# ESP32_S3.net
KiCad netlist of a schematic drawn in EasyEDA Pro
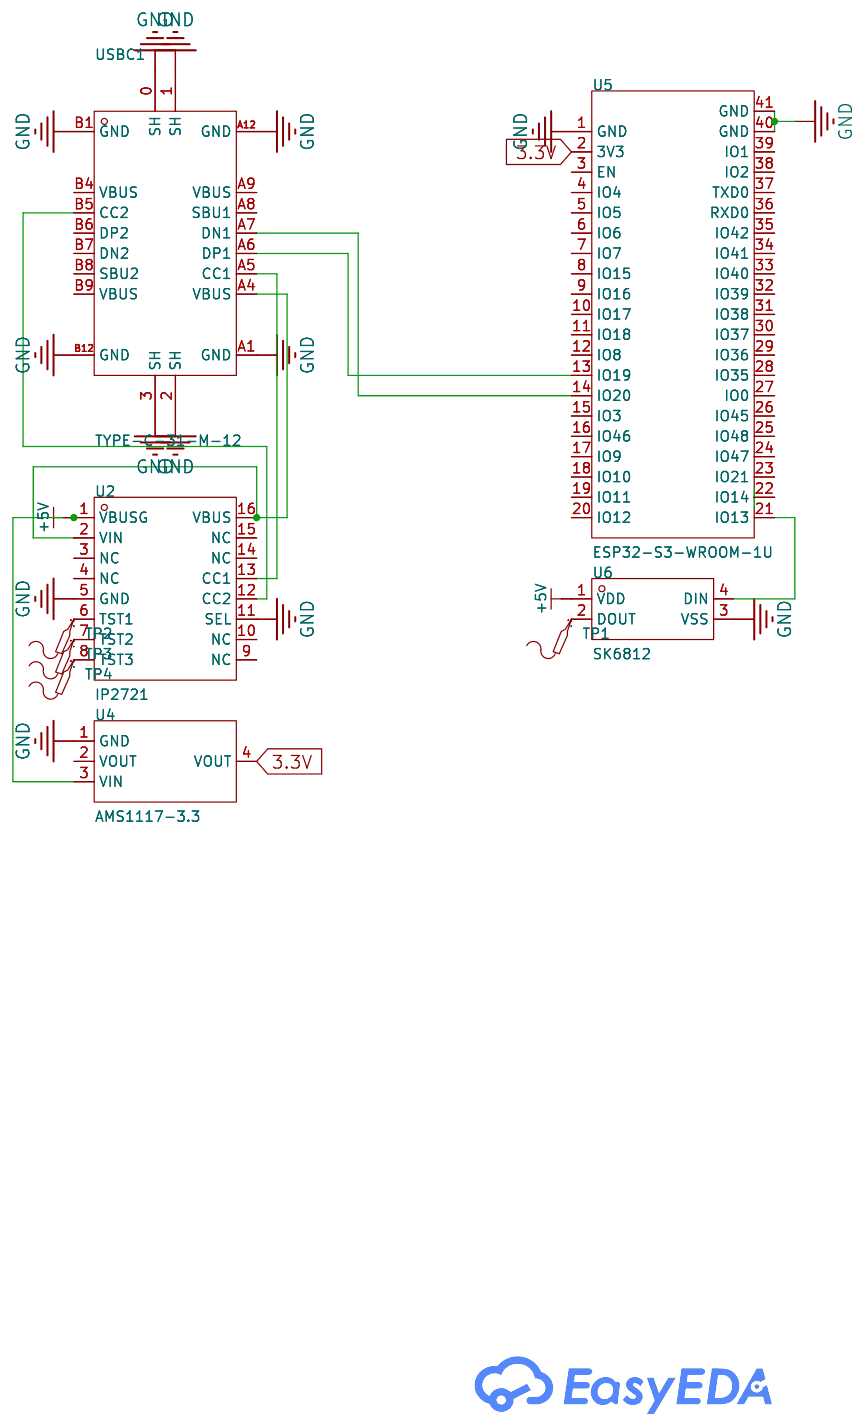
[diagram p0: schematic sheet]

(export (version "E")
  (design (tool "Eeschema 10.0.6"))
  (components
    (comp (ref "TP1")
      (value "~")
      (footprint "easyedapro:Test-Point-0.5mm")
      (description "Test Point 测试点")
      (libsource (lib "easyedapro") (part "Test-Point"))
    )
    (comp (ref "TP2")
      (value "~")
      (footprint "easyedapro:Test-Point-0.5mm")
      (description "Test Point 测试点")
      (libsource (lib "easyedapro") (part "Test-Point"))
    )
    (comp (ref "TP3")
      (value "~")
      (footprint "easyedapro:Test-Point-0.5mm")
      (description "Test Point 测试点")
      (libsource (lib "easyedapro") (part "Test-Point"))
    )
    (comp (ref "TP4")
      (value "~")
      (footprint "easyedapro:Test-Point-0.5mm")
      (description "Test Point 测试点")
      (libsource (lib "easyedapro") (part "Test-Point"))
    )
    (comp (ref "U2")
      (value "IP2721")
      (footprint "easyedapro:TSSOP-16_L5.0-W4.4-P0.65-LS6.4-BL")
      (fields (field (name "Manufacturer") "INJOINIC(英集芯)"))
      (libsource (lib "easyedapro") (part "IP2721"))
    )
    (comp (ref "U4")
      (value "AMS1117-3.3")
      (footprint "easyedapro:SOT-223-3_L6.5-W3.4-P2.30-LS7.0-BR")
      (fields (field (name "Manufacturer") "AMS"))
      (libsource (lib "easyedapro") (part "AMS1117-3.3"))
    )
    (comp (ref "U5")
      (value "ESP32-S3-WROOM-1U")
      (footprint "easyedapro:WIRELM-SMD_ESP32-S3-WROOM-1U")
      (libsource (lib "easyedapro") (part "ESP32-S3-WROOM-1U"))
    )
    (comp (ref "U6")
      (value "SK6812")
      (footprint "easyedapro:LED-SMD_4P-L5.0-W5.0-TL")
      (libsource (lib "easyedapro") (part "SK6812"))
    )
    (comp (ref "USBC1")
      (value "TYPE-C-31-M-12")
      (footprint "easyedapro:USB-C_SMD-TYPE-C-31-M-12")
      (fields (field (name "Manufacturer") "韩国韩荣"))
      (libsource (lib "easyedapro") (part "TYPE-C-31-M-12"))
    )
  )
  (nets
    (net (code "1") (name "+5V") (class "Default")
      (node (ref "U2") (pin "1") (pinfunction "VBUSG_1") (pintype "unspecified"))
      (node (ref "U4") (pin "3") (pinfunction "VIN_3") (pintype "unspecified"))
      (node (ref "U6") (pin "1") (pinfunction "VDD_1") (pintype "unspecified"))
    )
    (net (code "2") (name "3.3V") (class "Default")
      (node (ref "U4") (pin "4") (pinfunction "VOUT_4") (pintype "unspecified"))
      (node (ref "U5") (pin "2") (pinfunction "3V3_2") (pintype "unspecified"))
    )
    (net (code "3") (name "GND") (class "Default")
      (node (ref "U2") (pin "11") (pinfunction "SEL_11") (pintype "unspecified"))
      (node (ref "U2") (pin "5") (pinfunction "GND_5") (pintype "unspecified"))
      (node (ref "U4") (pin "1") (pinfunction "GND_1") (pintype "unspecified"))
      (node (ref "U5") (pin "1") (pinfunction "GND_1") (pintype "unspecified"))
      (node (ref "U5") (pin "40") (pinfunction "GND_40") (pintype "unspecified"))
      (node (ref "U5") (pin "41") (pinfunction "GND_41") (pintype "unspecified"))
      (node (ref "U6") (pin "3") (pinfunction "VSS_3") (pintype "unspecified"))
      (node (ref "USBC1") (pin "0") (pinfunction "SH_0") (pintype "unspecified"))
      (node (ref "USBC1") (pin "1") (pinfunction "SH_1") (pintype "unspecified"))
      (node (ref "USBC1") (pin "2") (pinfunction "SH_2") (pintype "unspecified"))
      (node (ref "USBC1") (pin "3") (pinfunction "SH_3") (pintype "unspecified"))
      (node (ref "USBC1") (pin "A1") (pinfunction "GND_A1") (pintype "unspecified"))
      (node (ref "USBC1") (pin "A12") (pinfunction "GND_A12") (pintype "unspecified"))
      (node (ref "USBC1") (pin "B1") (pinfunction "GND_B1") (pintype "unspecified"))
      (node (ref "USBC1") (pin "B12") (pinfunction "GND_B12") (pintype "unspecified"))
    )
    (net (code "4") (name "Net-(U2-CC1)") (class "Default")
      (node (ref "U2") (pin "13") (pinfunction "CC1_13") (pintype "unspecified"))
      (node (ref "USBC1") (pin "A5") (pinfunction "CC1_A5") (pintype "unspecified"))
    )
    (net (code "5") (name "Net-(U2-CC2)") (class "Default")
      (node (ref "U2") (pin "12") (pinfunction "CC2_12") (pintype "unspecified"))
      (node (ref "USBC1") (pin "B5") (pinfunction "CC2_B5") (pintype "unspecified"))
    )
    (net (code "6") (name "Net-(U2-TST1)") (class "Default")
      (node (ref "TP2") (pin "1") (pinfunction "1_1") (pintype "unspecified"))
      (node (ref "U2") (pin "6") (pinfunction "TST1_6") (pintype "unspecified"))
    )
    (net (code "7") (name "Net-(U2-TST2)") (class "Default")
      (node (ref "TP3") (pin "1") (pinfunction "1_1") (pintype "unspecified"))
      (node (ref "U2") (pin "7") (pinfunction "TST2_7") (pintype "unspecified"))
    )
    (net (code "8") (name "Net-(U2-TST3)") (class "Default")
      (node (ref "TP4") (pin "1") (pinfunction "1_1") (pintype "unspecified"))
      (node (ref "U2") (pin "8") (pinfunction "TST3_8") (pintype "unspecified"))
    )
    (net (code "9") (name "Net-(U2-VBUS)") (class "Default")
      (node (ref "U2") (pin "16") (pinfunction "VBUS_16") (pintype "unspecified"))
      (node (ref "U2") (pin "2") (pinfunction "VIN_2") (pintype "unspecified"))
      (node (ref "USBC1") (pin "A4") (pinfunction "VBUS_A4") (pintype "unspecified"))
    )
    (net (code "10") (name "Net-(U5-IO13)") (class "Default")
      (node (ref "U5") (pin "21") (pinfunction "IO13_21") (pintype "unspecified"))
      (node (ref "U6") (pin "4") (pinfunction "DIN_4") (pintype "unspecified"))
    )
    (net (code "11") (name "Net-(U5-IO19)") (class "Default")
      (node (ref "U5") (pin "13") (pinfunction "IO19_13") (pintype "unspecified"))
      (node (ref "USBC1") (pin "A6") (pinfunction "DP1_A6") (pintype "unspecified"))
    )
    (net (code "12") (name "Net-(U5-IO20)") (class "Default")
      (node (ref "U5") (pin "14") (pinfunction "IO20_14") (pintype "unspecified"))
      (node (ref "USBC1") (pin "A7") (pinfunction "DN1_A7") (pintype "unspecified"))
    )
    (net (code "13") (name "Net-(U6-DOUT)") (class "Default")
      (node (ref "TP1") (pin "1") (pinfunction "1_1") (pintype "unspecified"))
      (node (ref "U6") (pin "2") (pinfunction "DOUT_2") (pintype "unspecified"))
    )
    (net (code "14") (name "unconnected-(U2-NC-Pad3)") (class "Default")
      (node (ref "U2") (pin "3") (pinfunction "NC_3") (pintype "unspecified"))
    )
    (net (code "15") (name "unconnected-(U2-NC-Pad4)") (class "Default")
      (node (ref "U2") (pin "4") (pinfunction "NC_4") (pintype "unspecified"))
    )
    (net (code "16") (name "unconnected-(U2-NC-Pad9)") (class "Default")
      (node (ref "U2") (pin "9") (pinfunction "NC_9") (pintype "unspecified"))
    )
    (net (code "17") (name "unconnected-(U2-NC-Pad10)") (class "Default")
      (node (ref "U2") (pin "10") (pinfunction "NC_10") (pintype "unspecified"))
    )
    (net (code "18") (name "unconnected-(U2-NC-Pad14)") (class "Default")
      (node (ref "U2") (pin "14") (pinfunction "NC_14") (pintype "unspecified"))
    )
    (net (code "19") (name "unconnected-(U2-NC-Pad15)") (class "Default")
      (node (ref "U2") (pin "15") (pinfunction "NC_15") (pintype "unspecified"))
    )
    (net (code "20") (name "unconnected-(U4-VOUT-Pad2)") (class "Default")
      (node (ref "U4") (pin "2") (pinfunction "VOUT_2") (pintype "unspecified"))
    )
    (net (code "21") (name "unconnected-(U5-EN-Pad3)") (class "Default")
      (node (ref "U5") (pin "3") (pinfunction "EN_3") (pintype "unspecified"))
    )
    (net (code "22") (name "unconnected-(U5-IO0-Pad27)") (class "Default")
      (node (ref "U5") (pin "27") (pinfunction "IO0_27") (pintype "unspecified"))
    )
    (net (code "23") (name "unconnected-(U5-IO1-Pad39)") (class "Default")
      (node (ref "U5") (pin "39") (pinfunction "IO1_39") (pintype "unspecified"))
    )
    (net (code "24") (name "unconnected-(U5-IO2-Pad38)") (class "Default")
      (node (ref "U5") (pin "38") (pinfunction "IO2_38") (pintype "unspecified"))
    )
    (net (code "25") (name "unconnected-(U5-IO3-Pad15)") (class "Default")
      (node (ref "U5") (pin "15") (pinfunction "IO3_15") (pintype "unspecified"))
    )
    (net (code "26") (name "unconnected-(U5-IO4-Pad4)") (class "Default")
      (node (ref "U5") (pin "4") (pinfunction "IO4_4") (pintype "unspecified"))
    )
    (net (code "27") (name "unconnected-(U5-IO5-Pad5)") (class "Default")
      (node (ref "U5") (pin "5") (pinfunction "IO5_5") (pintype "unspecified"))
    )
    (net (code "28") (name "unconnected-(U5-IO6-Pad6)") (class "Default")
      (node (ref "U5") (pin "6") (pinfunction "IO6_6") (pintype "unspecified"))
    )
    (net (code "29") (name "unconnected-(U5-IO7-Pad7)") (class "Default")
      (node (ref "U5") (pin "7") (pinfunction "IO7_7") (pintype "unspecified"))
    )
    (net (code "30") (name "unconnected-(U5-IO8-Pad12)") (class "Default")
      (node (ref "U5") (pin "12") (pinfunction "IO8_12") (pintype "unspecified"))
    )
    (net (code "31") (name "unconnected-(U5-IO9-Pad17)") (class "Default")
      (node (ref "U5") (pin "17") (pinfunction "IO9_17") (pintype "unspecified"))
    )
    (net (code "32") (name "unconnected-(U5-IO10-Pad18)") (class "Default")
      (node (ref "U5") (pin "18") (pinfunction "IO10_18") (pintype "unspecified"))
    )
    (net (code "33") (name "unconnected-(U5-IO11-Pad19)") (class "Default")
      (node (ref "U5") (pin "19") (pinfunction "IO11_19") (pintype "unspecified"))
    )
    (net (code "34") (name "unconnected-(U5-IO12-Pad20)") (class "Default")
      (node (ref "U5") (pin "20") (pinfunction "IO12_20") (pintype "unspecified"))
    )
    (net (code "35") (name "unconnected-(U5-IO14-Pad22)") (class "Default")
      (node (ref "U5") (pin "22") (pinfunction "IO14_22") (pintype "unspecified"))
    )
    (net (code "36") (name "unconnected-(U5-IO15-Pad8)") (class "Default")
      (node (ref "U5") (pin "8") (pinfunction "IO15_8") (pintype "unspecified"))
    )
    (net (code "37") (name "unconnected-(U5-IO16-Pad9)") (class "Default")
      (node (ref "U5") (pin "9") (pinfunction "IO16_9") (pintype "unspecified"))
    )
    (net (code "38") (name "unconnected-(U5-IO17-Pad10)") (class "Default")
      (node (ref "U5") (pin "10") (pinfunction "IO17_10") (pintype "unspecified"))
    )
    (net (code "39") (name "unconnected-(U5-IO18-Pad11)") (class "Default")
      (node (ref "U5") (pin "11") (pinfunction "IO18_11") (pintype "unspecified"))
    )
    (net (code "40") (name "unconnected-(U5-IO21-Pad23)") (class "Default")
      (node (ref "U5") (pin "23") (pinfunction "IO21_23") (pintype "unspecified"))
    )
    (net (code "41") (name "unconnected-(U5-IO35-Pad28)") (class "Default")
      (node (ref "U5") (pin "28") (pinfunction "IO35_28") (pintype "unspecified"))
    )
    (net (code "42") (name "unconnected-(U5-IO36-Pad29)") (class "Default")
      (node (ref "U5") (pin "29") (pinfunction "IO36_29") (pintype "unspecified"))
    )
    (net (code "43") (name "unconnected-(U5-IO37-Pad30)") (class "Default")
      (node (ref "U5") (pin "30") (pinfunction "IO37_30") (pintype "unspecified"))
    )
    (net (code "44") (name "unconnected-(U5-IO38-Pad31)") (class "Default")
      (node (ref "U5") (pin "31") (pinfunction "IO38_31") (pintype "unspecified"))
    )
    (net (code "45") (name "unconnected-(U5-IO39-Pad32)") (class "Default")
      (node (ref "U5") (pin "32") (pinfunction "IO39_32") (pintype "unspecified"))
    )
    (net (code "46") (name "unconnected-(U5-IO40-Pad33)") (class "Default")
      (node (ref "U5") (pin "33") (pinfunction "IO40_33") (pintype "unspecified"))
    )
    (net (code "47") (name "unconnected-(U5-IO41-Pad34)") (class "Default")
      (node (ref "U5") (pin "34") (pinfunction "IO41_34") (pintype "unspecified"))
    )
    (net (code "48") (name "unconnected-(U5-IO42-Pad35)") (class "Default")
      (node (ref "U5") (pin "35") (pinfunction "IO42_35") (pintype "unspecified"))
    )
    (net (code "49") (name "unconnected-(U5-IO45-Pad26)") (class "Default")
      (node (ref "U5") (pin "26") (pinfunction "IO45_26") (pintype "unspecified"))
    )
    (net (code "50") (name "unconnected-(U5-IO46-Pad16)") (class "Default")
      (node (ref "U5") (pin "16") (pinfunction "IO46_16") (pintype "unspecified"))
    )
    (net (code "51") (name "unconnected-(U5-IO47-Pad24)") (class "Default")
      (node (ref "U5") (pin "24") (pinfunction "IO47_24") (pintype "unspecified"))
    )
    (net (code "52") (name "unconnected-(U5-IO48-Pad25)") (class "Default")
      (node (ref "U5") (pin "25") (pinfunction "IO48_25") (pintype "unspecified"))
    )
    (net (code "53") (name "unconnected-(U5-RXD0-Pad36)") (class "Default")
      (node (ref "U5") (pin "36") (pinfunction "RXD0_36") (pintype "unspecified"))
    )
    (net (code "54") (name "unconnected-(U5-TXD0-Pad37)") (class "Default")
      (node (ref "U5") (pin "37") (pinfunction "TXD0_37") (pintype "unspecified"))
    )
    (net (code "55") (name "unconnected-(USBC1-DN2-PadB7)") (class "Default")
      (node (ref "USBC1") (pin "B7") (pinfunction "DN2_B7") (pintype "unspecified"))
    )
    (net (code "56") (name "unconnected-(USBC1-DP2-PadB6)") (class "Default")
      (node (ref "USBC1") (pin "B6") (pinfunction "DP2_B6") (pintype "unspecified"))
    )
    (net (code "57") (name "unconnected-(USBC1-SBU1-PadA8)") (class "Default")
      (node (ref "USBC1") (pin "A8") (pinfunction "SBU1_A8") (pintype "unspecified"))
    )
    (net (code "58") (name "unconnected-(USBC1-SBU2-PadB8)") (class "Default")
      (node (ref "USBC1") (pin "B8") (pinfunction "SBU2_B8") (pintype "unspecified"))
    )
    (net (code "59") (name "unconnected-(USBC1-VBUS-PadA9)") (class "Default")
      (node (ref "USBC1") (pin "A9") (pinfunction "VBUS_A9") (pintype "unspecified"))
    )
    (net (code "60") (name "unconnected-(USBC1-VBUS-PadB4)") (class "Default")
      (node (ref "USBC1") (pin "B4") (pinfunction "VBUS_B4") (pintype "unspecified"))
    )
    (net (code "61") (name "unconnected-(USBC1-VBUS-PadB9)") (class "Default")
      (node (ref "USBC1") (pin "B9") (pinfunction "VBUS_B9") (pintype "unspecified"))
    )
  )
)
